# 1u_panel.net
KiCad netlist of a schematic drawn in EAGLE
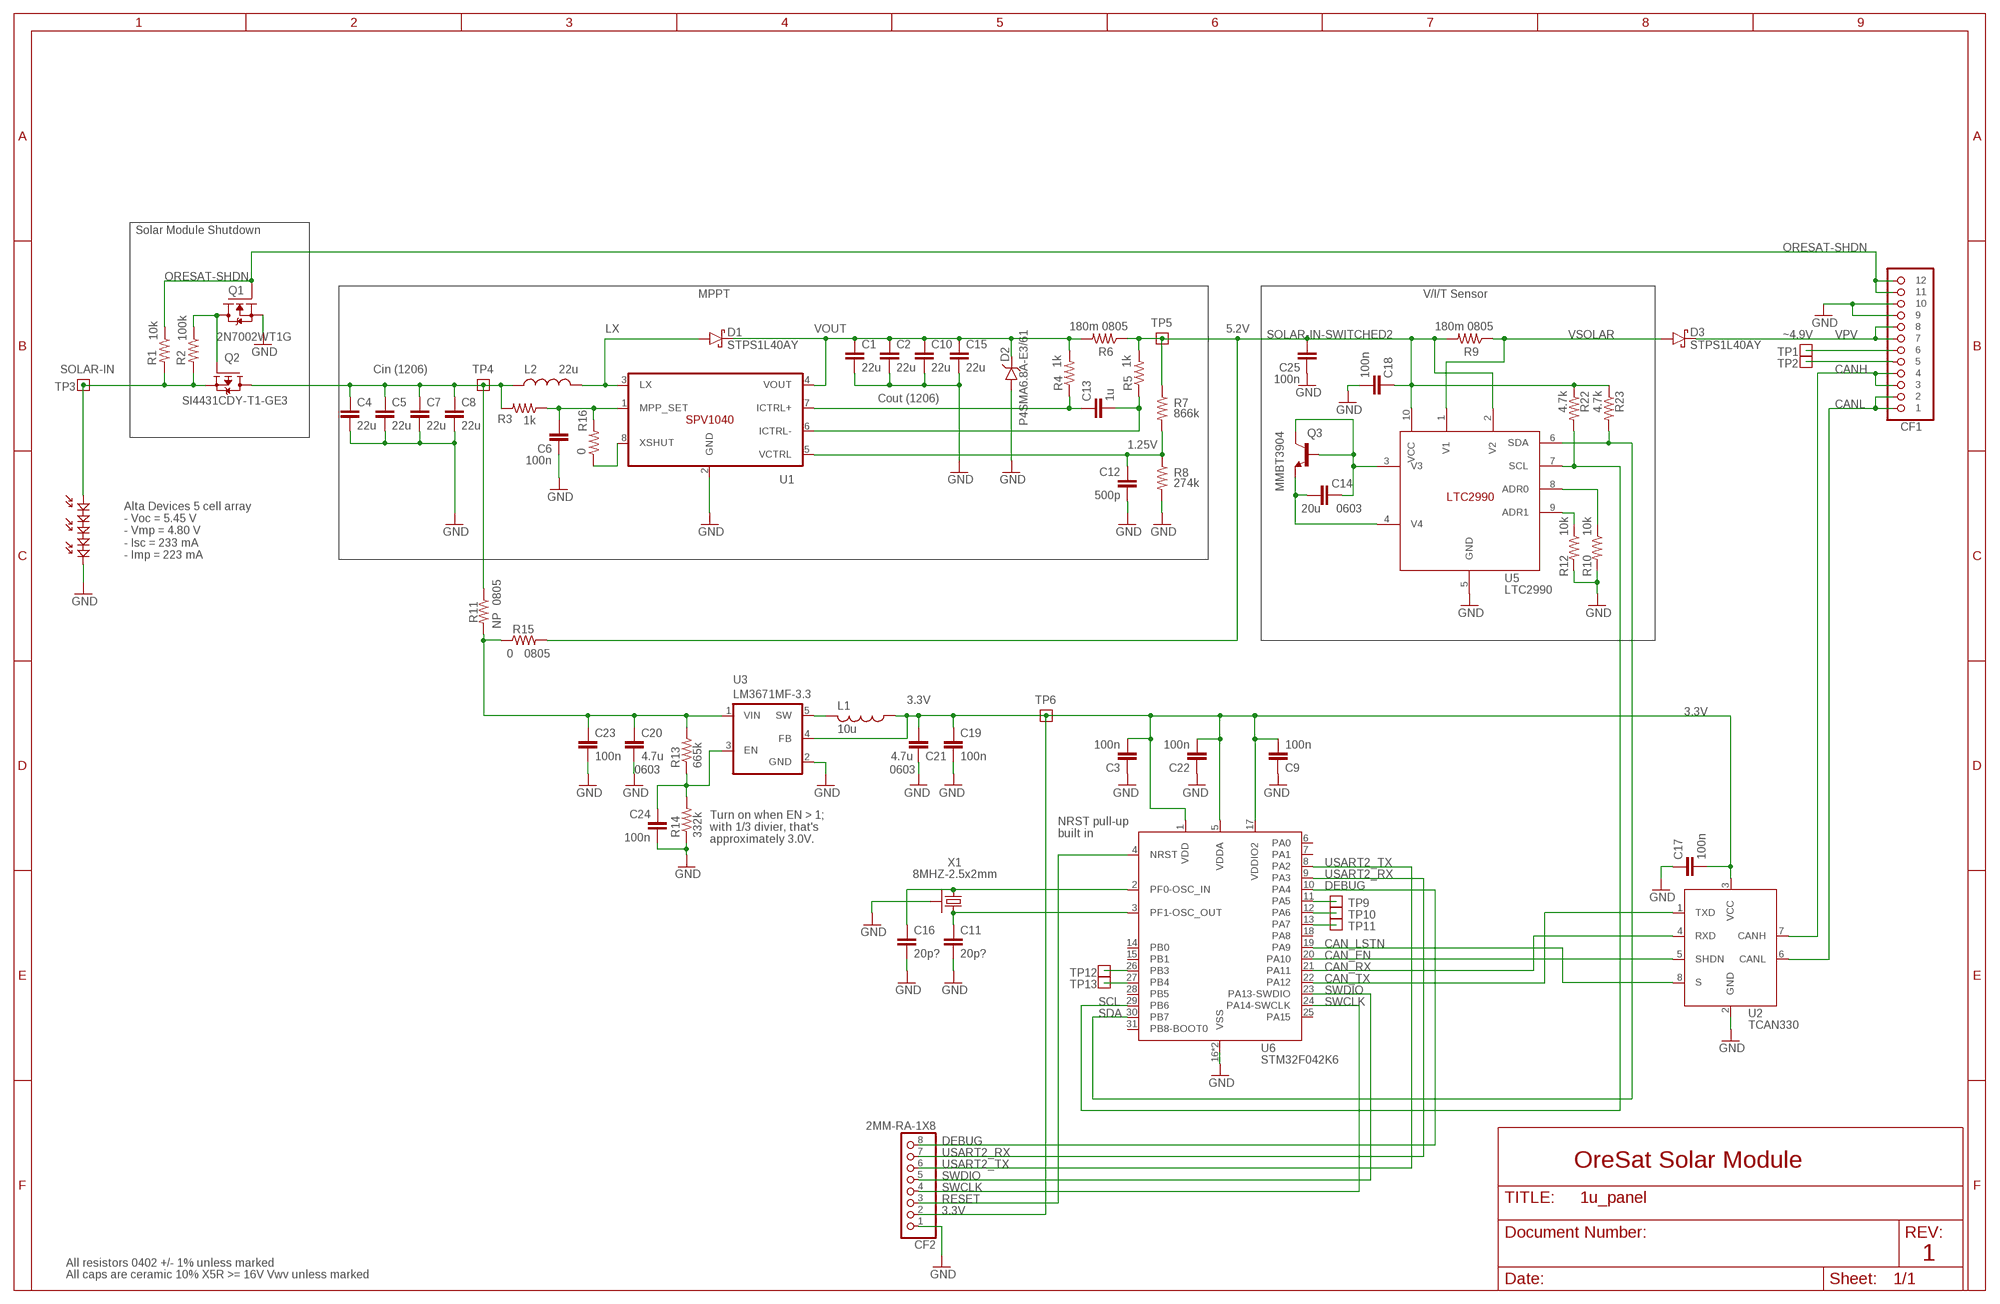
[diagram p0: schematic, sheet 1]

(export (version "E")
  (design (tool "Eeschema 10.0.6"))
  (components
    (comp (ref "C1")
      (value "22u")
      (footprint "eagle-import:1206-B")
      (fields (field (name "MFR") "Murata") (field (name "MPN") "GRM31CR71A226KE15L"))
      (libsource (lib "eagle-import") (part "C-EU1206-B"))
    )
    (comp (ref "C2")
      (value "22u")
      (footprint "eagle-import:1206-B")
      (fields (field (name "MFR") "Murata") (field (name "MPN") "GRM31CR71A226KE15L"))
      (libsource (lib "eagle-import") (part "C-EU1206-B"))
    )
    (comp (ref "C3")
      (value "100n")
      (footprint "eagle-import:.0402-B-NOSILK")
      (fields
        (field (name "MFR") "   Samsung Electro-Mechanics America, Inc.")
        (field (name "MPN") "CL05B104KO5NNNC")
      )
      (libsource (lib "eagle-import") (part "C-EU0402-B-NOSILK"))
    )
    (comp (ref "C4")
      (value "22u")
      (footprint "eagle-import:1206-B")
      (fields (field (name "MFR") "Murata") (field (name "MPN") "GRM31CR71A226KE15L"))
      (libsource (lib "eagle-import") (part "C-EU1206-B"))
    )
    (comp (ref "C5")
      (value "22u")
      (footprint "eagle-import:1206-B")
      (fields (field (name "MFR") "Murata") (field (name "MPN") "GRM31CR71A226KE15L"))
      (libsource (lib "eagle-import") (part "C-EU1206-B"))
    )
    (comp (ref "C6")
      (value "100n")
      (footprint "eagle-import:.0402-B-NOSILK")
      (fields
        (field (name "MFR") "   Samsung Electro-Mechanics America, Inc. ")
        (field (name "MPN") " CL05B104KO5NNNC")
      )
      (libsource (lib "eagle-import") (part "C-EU0402-B-NOSILK"))
    )
    (comp (ref "C7")
      (value "22u")
      (footprint "eagle-import:1206-B")
      (fields (field (name "MFR") "Murata") (field (name "MPN") "GRM31CR71A226KE15L"))
      (libsource (lib "eagle-import") (part "C-EU1206-B"))
    )
    (comp (ref "C8")
      (value "22u")
      (footprint "eagle-import:1206-B")
      (fields (field (name "MFR") "Murata") (field (name "MPN") "GRM31CR71A226KE15L"))
      (libsource (lib "eagle-import") (part "C-EU1206-B"))
    )
    (comp (ref "C9")
      (value "100n")
      (footprint "eagle-import:.0402-B-NOSILK")
      (fields
        (field (name "MFR") "Samsung Electro-Mechanics America, Inc.")
        (field (name "MPN") " CL05B104KO5NNNC")
      )
      (libsource (lib "eagle-import") (part "C-EU0402-B-NOSILK"))
    )
    (comp (ref "C10")
      (value "22u")
      (footprint "eagle-import:1206-B")
      (fields (field (name "MFR") "Murata") (field (name "MPN") "GRM31CR71A226KE15L"))
      (libsource (lib "eagle-import") (part "C-EU1206-B"))
    )
    (comp (ref "C11")
      (value "20p?")
      (footprint "eagle-import:.0402-B-NOSILK")
      (libsource (lib "eagle-import") (part "C-EU0402-B-NOSILK"))
    )
    (comp (ref "C12")
      (value "500p")
      (footprint "eagle-import:.0402-B-NOSILK")
      (fields
        (field (name "MFR") "Samsung Electro-Mechanics America, Inc.")
        (field (name "MPN") "CL05B561KB5NNNC")
      )
      (libsource (lib "eagle-import") (part "C-EU0402-B-NOSILK"))
    )
    (comp (ref "C13")
      (value "1u")
      (footprint "eagle-import:.0402-B-NOSILK")
      (fields
        (field (name "MFR") "Samsung Electro-Mechanics America, Inc.")
        (field (name "MPN") " CL05A105KA5NQNC")
      )
      (libsource (lib "eagle-import") (part "C-EU0402-B-NOSILK"))
    )
    (comp (ref "C14")
      (value "20u")
      (footprint "eagle-import:.0603-B-NOSILK")
      (fields
        (field (name "MFR") "Samsung Electro-Mechanics America, Inc.")
        (field (name "MPN") " CL10A226MP8NUNE")
      )
      (libsource (lib "eagle-import") (part "C-EU0603-B-NOSILK"))
    )
    (comp (ref "C15")
      (value "22u")
      (footprint "eagle-import:1206-B")
      (fields (field (name "MFR") "Murata") (field (name "MPN") "GRM31CR71A226KE15L"))
      (libsource (lib "eagle-import") (part "C-EU1206-B"))
    )
    (comp (ref "C16")
      (value "20p?")
      (footprint "eagle-import:.0402-B-NOSILK")
      (libsource (lib "eagle-import") (part "C-EU0402-B-NOSILK"))
    )
    (comp (ref "C17")
      (value "100n")
      (footprint "eagle-import:.0402-B-NOSILK")
      (fields
        (field (name "MFR") "Samsung Electro-Mechanics America, Inc.")
        (field (name "MPN") "CL05B104KO5NNNC")
      )
      (libsource (lib "eagle-import") (part "C-EU0402-B-NOSILK"))
    )
    (comp (ref "C18")
      (value "100n")
      (footprint "eagle-import:.0402-B-NOSILK")
      (fields
        (field (name "MFR") "Samsung Electro-Mechanics America, Inc.")
        (field (name "MPN") "CL05B104KO5NNNC")
      )
      (libsource (lib "eagle-import") (part "C-EU0402-B-NOSILK"))
    )
    (comp (ref "C19")
      (value "100n")
      (footprint "eagle-import:.0402-B-NOSILK")
      (fields
        (field (name "MFR") "   Samsung Electro-Mechanics America, Inc.")
        (field (name "MPN") "CL05B104KO5NNNC")
      )
      (libsource (lib "eagle-import") (part "C-EU0402-B-NOSILK"))
    )
    (comp (ref "C20")
      (value "4.7u")
      (footprint "eagle-import:C0603")
      (fields
        (field (name "MFR") "Samsung Electro-Mechanics America, Inc.")
        (field (name "MPN") "CL05B104KO5NNNC")
      )
      (libsource (lib "eagle-import") (part "C-EUC0603"))
    )
    (comp (ref "C21")
      (value "4.7u")
      (footprint "eagle-import:C0603")
      (fields
        (field (name "MFR") "   Samsung Electro-Mechanics America, Inc. ")
        (field (name "MPN") "CL05B104KO5NNNC")
      )
      (libsource (lib "eagle-import") (part "C-EUC0603"))
    )
    (comp (ref "C22")
      (value "100n")
      (footprint "eagle-import:.0402-B-NOSILK")
      (fields
        (field (name "MFR") "Samsung Electro-Mechanics America, Inc.")
        (field (name "MPN") "CL05B104KO5NNNC")
      )
      (libsource (lib "eagle-import") (part "C-EU0402-B-NOSILK"))
    )
    (comp (ref "C23")
      (value "100n")
      (footprint "eagle-import:.0402-B-NOSILK")
      (fields
        (field (name "MFR") "Samsung Electro-Mechanics America, Inc.")
        (field (name "MPN") "CL05B104KO5NNNC")
      )
      (libsource (lib "eagle-import") (part "C-EU0402-B-NOSILK"))
    )
    (comp (ref "C24")
      (value "100n")
      (footprint "eagle-import:.0402-B-NOSILK")
      (fields
        (field (name "MFR") "Samsung Electro-Mechanics America, Inc.")
        (field (name "MPN") "CL05B104KO5NNNC")
      )
      (libsource (lib "eagle-import") (part "C-EU0402-B-NOSILK"))
    )
    (comp (ref "C25")
      (value "100n")
      (footprint "eagle-import:.0402-B-NOSILK")
      (fields
        (field (name "MFR") "Samsung Electro-Mechanics America, Inc.")
        (field (name "MPN") " CL05B104KO5NNNC")
      )
      (libsource (lib "eagle-import") (part "C-EU0402-B-NOSILK"))
    )
    (comp (ref "CF1")
      (value "ORESAT-SOLARPANEL-12PIN")
      (footprint "eagle-import:CON-1.27-F-HARTING-1522012X601XXX")
      (libsource (lib "eagle-import") (part "ORESAT-SOLARPANEL-12PIN"))
    )
    (comp (ref "CF2")
      (value "2MM-RA-1X8")
      (footprint "eagle-import:CF-2MM-RA-1X8-PRECIDIP-831")
      (fields (field (name "MPN") "831-87-050-40-001101"))
      (libsource (lib "eagle-import") (part "2MM-RA-1X8"))
    )
    (comp (ref "D1")
      (value "STPS1L40AY")
      (footprint "eagle-import:DO214AC")
      (fields (field (name "MFR") "ST"))
      (libsource (lib "eagle-import") (part "DIODE-DO214AC"))
    )
    (comp (ref "D2")
      (value "P4SMA6.8A-E3/61")
      (footprint "eagle-import:DO214AC")
      (fields (field (name "MFR") "Vishay"))
      (libsource (lib "eagle-import") (part "diode-zener-tvs_DIODE-DO214AC"))
    )
    (comp (ref "D3")
      (value "STPS1L40AY")
      (footprint "eagle-import:DO214AC")
      (fields (field (name "MFR") "ST"))
      (libsource (lib "eagle-import") (part "DIODE-DO214AC"))
    )
    (comp (ref "L1")
      (value "10u")
      (footprint "eagle-import:L2012C")
      (fields (field (name "MFR") "Taiyo Yuden") (field (name "MPN") " CB2012T100KR"))
      (libsource (lib "eagle-import") (part "L-USL2012C"))
    )
    (comp (ref "L2")
      (value "22u")
      (footprint "eagle-import:VISHAY-DALE-IFSR-1515AHER")
      (fields (field (name "MFR") "Vishay Dale") (field (name "MPN") "IFSC1515AHER220M01"))
      (libsource (lib "eagle-import") (part "L-VISHAY-DALE-IFSC-1515AHER"))
    )
    (comp (ref "PV1")
      (value "ALTA-5-CELL-ARRAYALTA-FIVE-CELL-SLOT")
      (footprint "eagle-import:ALTA-FIVE-CELL-THROUGH-SLOT")
      (libsource (lib "eagle-import") (part "ALTA-5-CELL-ARRAYALTA-FIVE-CELL-SLOT"))
    )
    (comp (ref "Q1")
      (value "2N7002WT1G")
      (footprint "eagle-import:SOT23")
      (fields (field (name "MFR") "rer   ON Semiconductor"))
      (libsource (lib "eagle-import") (part "ON-N-CHANNEL-FET"))
    )
    (comp (ref "Q2")
      (value "SI4431CDY-T1-GE3")
      (footprint "eagle-import:SO8")
      (fields (field (name "MFR") "Vishay Siliconix") (field (name "MPN") "   SI4431CDY-T1-GE3"))
      (libsource (lib "eagle-import") (part "P-CHANNELFET"))
    )
    (comp (ref "Q3")
      (value "MMBT3904")
      (footprint "eagle-import:SOT23HOLE")
      (fields (field (name "MFR") "   Fairchild/ON Semiconductor"))
      (libsource (lib "eagle-import") (part "DIODE-INC-NPNSOT23HOLE"))
    )
    (comp (ref "R1")
      (value "10k")
      (footprint "eagle-import:.0402-B-NOSILK")
      (fields (field (name "MFR") "Rohm Semiconductor") (field (name "MPN") "MCR01MZPF1002"))
      (libsource (lib "eagle-import") (part "R-US_0402-B-NOSILK"))
    )
    (comp (ref "R2")
      (value "100k")
      (footprint "eagle-import:.0402-B-NOSILK")
      (fields (field (name "MFR") "Rohm Semiconductor") (field (name "MPN") "MCR01MRTF1003"))
      (libsource (lib "eagle-import") (part "R-US_0402-B-NOSILK"))
    )
    (comp (ref "R3")
      (value "1k")
      (footprint "eagle-import:.0402-B-NOSILK")
      (fields (field (name "MPN") " MCR01MZPF1001"))
      (libsource (lib "eagle-import") (part "R-US_0402-B-NOSILK"))
    )
    (comp (ref "R4")
      (value "1k")
      (footprint "eagle-import:.0402-B-NOSILK")
      (libsource (lib "eagle-import") (part "R-US_0402-B-NOSILK"))
    )
    (comp (ref "R5")
      (value "1k")
      (footprint "eagle-import:.0402-B-NOSILK")
      (libsource (lib "eagle-import") (part "R-US_0402-B-NOSILK"))
    )
    (comp (ref "R6")
      (value "180m 0805")
      (footprint "eagle-import:.0805-B-NOSILK")
      (fields (field (name "MFR") "Vishay Dale") (field (name "MPN") "RCWE0805R180FKEA"))
      (libsource (lib "eagle-import") (part "R-US_0805-B-NOSILK"))
    )
    (comp (ref "R7")
      (value "866k")
      (footprint "eagle-import:.0402-B-NOSILK")
      (fields (field (name "MPN") "RC1005F8663CS"))
      (libsource (lib "eagle-import") (part "R-US_0402-B-NOSILK"))
    )
    (comp (ref "R8")
      (value "274k")
      (footprint "eagle-import:.0402-B-NOSILK")
      (fields (field (name "MFR") "Vishay Dale") (field (name "MPN") "CRCW0402274KFKED"))
      (libsource (lib "eagle-import") (part "R-US_0402-B-NOSILK"))
    )
    (comp (ref "R9")
      (value "180m 0805")
      (footprint "eagle-import:.0805-B-NOSILK")
      (fields (field (name "MFR") "Vishay Dale") (field (name "MPN") "RCWE0805R180FKEA"))
      (libsource (lib "eagle-import") (part "R-US_0805-B-NOSILK"))
    )
    (comp (ref "R10")
      (value "10k")
      (footprint "eagle-import:.0402-B-NOSILK")
      (fields (field (name "MFR") "Rohm Semiconductor") (field (name "MPN") " MCR01MZPF1002"))
      (libsource (lib "eagle-import") (part "R-US_0402-B-NOSILK"))
    )
    (comp (ref "R11")
      (value "NP")
      (footprint "eagle-import:.0805-B-NOSILK")
      (libsource (lib "eagle-import") (part "R-US_0805-B-NOSILK"))
    )
    (comp (ref "R12")
      (value "10k")
      (footprint "eagle-import:.0402-B-NOSILK")
      (fields (field (name "MFR") "Rohm Semiconductor") (field (name "MPN") "MCR01MZPF1002"))
      (libsource (lib "eagle-import") (part "R-US_0402-B-NOSILK"))
    )
    (comp (ref "R13")
      (value "665k")
      (footprint "eagle-import:.0402-B-NOSILK")
      (fields
        (field (name "MFR") "Samsung Electro-Mechanics America, Inc.")
        (field (name "MPN") "RC1005F6653CS")
      )
      (libsource (lib "eagle-import") (part "R-US_0402-B-NOSILK"))
    )
    (comp (ref "R14")
      (value "332k")
      (footprint "eagle-import:.0402-B-NOSILK")
      (fields
        (field (name "MFR") "Samsung Electro-Mechanics America, Inc.")
        (field (name "MPN") " RC1005F3323CS")
      )
      (libsource (lib "eagle-import") (part "R-US_0402-B-NOSILK"))
    )
    (comp (ref "R15")
      (value "0")
      (footprint "eagle-import:.0805-B-NOSILK")
      (libsource (lib "eagle-import") (part "R-US_0805-B-NOSILK"))
    )
    (comp (ref "R16")
      (value "0")
      (footprint "eagle-import:.0402-B-NOSILK")
      (libsource (lib "eagle-import") (part "R-US_0402-B-NOSILK"))
    )
    (comp (ref "R22")
      (value "4.7k")
      (footprint "eagle-import:.0402-B-NOSILK")
      (fields (field (name "MFR") "Rohm Semiconductor") (field (name "MPN") "TRR01MZPF4701"))
      (libsource (lib "eagle-import") (part "R-US_0402-B-NOSILK"))
    )
    (comp (ref "R23")
      (value "4.7k")
      (footprint "eagle-import:.0402-B-NOSILK")
      (fields (field (name "MFR") "Rohm Semiconductor") (field (name "MPN") "TRR01MZPF4701"))
      (libsource (lib "eagle-import") (part "R-US_0402-B-NOSILK"))
    )
    (comp (ref "TP1")
      (value "TEST-POINT")
      (footprint "eagle-import:2MM-TEST-POINT")
      (libsource (lib "eagle-import") (part "TEST-POINT"))
    )
    (comp (ref "TP2")
      (value "TEST-POINT")
      (footprint "eagle-import:2MM-TEST-POINT")
      (libsource (lib "eagle-import") (part "TEST-POINT"))
    )
    (comp (ref "TP3")
      (value "TEST-POINT")
      (footprint "eagle-import:2MM-TEST-POINT")
      (libsource (lib "eagle-import") (part "TEST-POINT"))
    )
    (comp (ref "TP4")
      (value "TEST-POINT")
      (footprint "eagle-import:2MM-TEST-POINT")
      (libsource (lib "eagle-import") (part "TEST-POINT"))
    )
    (comp (ref "TP5")
      (value "TEST-POINT")
      (footprint "eagle-import:2MM-TEST-POINT")
      (libsource (lib "eagle-import") (part "TEST-POINT"))
    )
    (comp (ref "TP6")
      (value "TEST-POINT")
      (footprint "eagle-import:2MM-TEST-POINT")
      (libsource (lib "eagle-import") (part "TEST-POINT"))
    )
    (comp (ref "TP9")
      (value "TEST-POINT")
      (footprint "eagle-import:2MM-TEST-POINT")
      (libsource (lib "eagle-import") (part "TEST-POINT"))
    )
    (comp (ref "TP10")
      (value "TEST-POINT")
      (footprint "eagle-import:2MM-TEST-POINT")
      (libsource (lib "eagle-import") (part "TEST-POINT"))
    )
    (comp (ref "TP11")
      (value "TEST-POINT")
      (footprint "eagle-import:2MM-TEST-POINT")
      (libsource (lib "eagle-import") (part "TEST-POINT"))
    )
    (comp (ref "TP12")
      (value "TEST-POINT")
      (footprint "eagle-import:2MM-TEST-POINT")
      (libsource (lib "eagle-import") (part "TEST-POINT"))
    )
    (comp (ref "TP13")
      (value "TEST-POINT")
      (footprint "eagle-import:2MM-TEST-POINT")
      (libsource (lib "eagle-import") (part "TEST-POINT"))
    )
    (comp (ref "U1")
      (value "SPV1040")
      (footprint "eagle-import:TSSOP-8")
      (fields (field (name "MFR") "STMicroelectronics") (field (name "MPN") "SPV1040T"))
      (libsource (lib "eagle-import") (part "SPV1040"))
    )
    (comp (ref "U2")
      (value "TCAN330")
      (footprint "eagle-import:SOT23-8_TI-DCN")
      (fields (field (name "MFR") "Texas Instruments") (field (name "MPN") "TCAN330GDCNT"))
      (libsource (lib "eagle-import") (part "TCAN330"))
    )
    (comp (ref "U3")
      (value "LM3671MF-3.3")
      (footprint "eagle-import:SOT23-5")
      (libsource (lib "eagle-import") (part "LM3761"))
    )
    (comp (ref "U5")
      (value "LTC2990")
      (footprint "eagle-import:MSOP10")
      (fields (field (name "MFR") "Linear Technology") (field (name "MPN") " LTC2990CMS#PBF"))
      (libsource (lib "eagle-import") (part "LTC2990"))
    )
    (comp (ref "U6")
      (value "STM32F042K6")
      (footprint "eagle-import:QFP32-7X7")
      (fields (field (name "MFR") "STMicroelectronics") (field (name "MPN") "STM32F042K6T6"))
      (libsource (lib "eagle-import") (part "STM32F042K6"))
    )
    (comp (ref "X1")
      (value "8MHZ-2.5x2mm")
      (footprint "eagle-import:CRYSTAL_2.5X2")
      (fields (field (name "MFR") "ECS Inc.") (field (name "MPN") "ECS-80-18-20BQ-DS"))
      (libsource (lib "eagle-import") (part "CRYSTAL-WITH-GND"))
    )
  )
  (nets
    (net (code "1") (name "/3.3V") (class "Default")
      (node (ref "C17") (pin "2") (pinfunction "2_2") (pintype "passive"))
      (node (ref "C19") (pin "1") (pinfunction "1_1") (pintype "passive"))
      (node (ref "C21") (pin "1") (pinfunction "1_1") (pintype "passive"))
      (node (ref "C22") (pin "2") (pinfunction "2_2") (pintype "passive"))
      (node (ref "C3") (pin "2") (pinfunction "2_2") (pintype "passive"))
      (node (ref "C9") (pin "2") (pinfunction "2_2") (pintype "passive"))
      (node (ref "CF2") (pin "2") (pinfunction "2_2") (pintype "passive"))
      (node (ref "L1") (pin "1") (pinfunction "1_1") (pintype "passive"))
      (node (ref "TP6") (pin "1") (pinfunction "1_1") (pintype "passive"))
      (node (ref "U2") (pin "3") (pinfunction "VCC_3") (pintype "power_in"))
      (node (ref "U3") (pin "4") (pinfunction "FB_4") (pintype "input"))
      (node (ref "U6") (pin "1") (pinfunction "VDD_1") (pintype "power_in"))
      (node (ref "U6") (pin "17") (pinfunction "VDDIO2_17") (pintype "power_in"))
      (node (ref "U6") (pin "5") (pinfunction "VDDA_5") (pintype "power_in"))
    )
    (net (code "2") (name "/CANH") (class "Default")
      (node (ref "CF1") (pin "3") (pinfunction "3_3") (pintype "passive"))
      (node (ref "CF1") (pin "4") (pinfunction "4_4") (pintype "passive"))
      (node (ref "U2") (pin "7") (pinfunction "CANH_7") (pintype "bidirectional"))
    )
    (net (code "3") (name "/CANL") (class "Default")
      (node (ref "CF1") (pin "1") (pinfunction "1_1") (pintype "passive"))
      (node (ref "CF1") (pin "2") (pinfunction "2_2") (pintype "passive"))
      (node (ref "U2") (pin "6") (pinfunction "CANL_6") (pintype "bidirectional"))
    )
    (net (code "4") (name "/CAN_EN") (class "Default")
      (node (ref "U2") (pin "5") (pinfunction "SHDN_5") (pintype "input"))
      (node (ref "U6") (pin "20") (pinfunction "PA10_20") (pintype "bidirectional"))
    )
    (net (code "5") (name "/CAN_LSTN") (class "Default")
      (node (ref "U2") (pin "8") (pinfunction "S_8") (pintype "input"))
      (node (ref "U6") (pin "19") (pinfunction "PA9_19") (pintype "bidirectional"))
    )
    (net (code "6") (name "/CAN_RX") (class "Default")
      (node (ref "U2") (pin "4") (pinfunction "RXD_4") (pintype "output"))
      (node (ref "U6") (pin "21") (pinfunction "PA11_21") (pintype "bidirectional"))
    )
    (net (code "7") (name "/CAN_TX") (class "Default")
      (node (ref "U2") (pin "1") (pinfunction "TXD_1") (pintype "input"))
      (node (ref "U6") (pin "22") (pinfunction "PA12_22") (pintype "bidirectional"))
    )
    (net (code "8") (name "/DEBUG") (class "Default")
      (node (ref "CF2") (pin "8") (pinfunction "8_8") (pintype "passive"))
      (node (ref "U6") (pin "10") (pinfunction "PA4_10") (pintype "bidirectional"))
    )
    (net (code "9") (name "/LX") (class "Default")
      (node (ref "D1") (pin "A") (pinfunction "A_A") (pintype "passive"))
      (node (ref "L2") (pin "1") (pinfunction "1_1") (pintype "passive"))
      (node (ref "U1") (pin "3") (pinfunction "LX_3") (pintype "input"))
    )
    (net (code "10") (name "/ORESAT-SHDN") (class "Default")
      (node (ref "CF1") (pin "11") (pinfunction "11_11") (pintype "passive"))
      (node (ref "CF1") (pin "12") (pinfunction "12_12") (pintype "passive"))
      (node (ref "Q1") (pin "1") (pinfunction "G_1") (pintype "passive"))
      (node (ref "R1") (pin "1") (pinfunction "1_1") (pintype "passive"))
    )
    (net (code "11") (name "/RESET") (class "Default")
      (node (ref "CF2") (pin "3") (pinfunction "3_3") (pintype "passive"))
      (node (ref "U6") (pin "4") (pinfunction "NRST_4") (pintype "bidirectional"))
    )
    (net (code "12") (name "/SCL") (class "Default")
      (node (ref "R22") (pin "2") (pinfunction "2_2") (pintype "passive"))
      (node (ref "U5") (pin "7") (pinfunction "SCL_7") (pintype "bidirectional"))
      (node (ref "U6") (pin "29") (pinfunction "PB6_29") (pintype "bidirectional"))
    )
    (net (code "13") (name "/SDA") (class "Default")
      (node (ref "R23") (pin "2") (pinfunction "2_2") (pintype "passive"))
      (node (ref "U5") (pin "6") (pinfunction "SDA_6") (pintype "bidirectional"))
      (node (ref "U6") (pin "30") (pinfunction "PB7_30") (pintype "bidirectional"))
    )
    (net (code "14") (name "/SOLAR-IN") (class "Default")
      (node (ref "PV1") (pin "POS1") (pinfunction "POS_POS1") (pintype "power_in"))
      (node (ref "PV1") (pin "POS2") (pinfunction "POS_POS2") (pintype "power_in"))
      (node (ref "Q2") (pin "1") (pinfunction "S_1") (pintype "passive"))
      (node (ref "Q2") (pin "2") (pinfunction "S_2") (pintype "passive"))
      (node (ref "Q2") (pin "3") (pinfunction "S_3") (pintype "passive"))
      (node (ref "R1") (pin "2") (pinfunction "2_2") (pintype "passive"))
      (node (ref "R2") (pin "2") (pinfunction "2_2") (pintype "passive"))
      (node (ref "TP3") (pin "1") (pinfunction "1_1") (pintype "passive"))
    )
    (net (code "15") (name "/SOLAR-IN-SWITCHED2") (class "Default")
      (node (ref "C18") (pin "1") (pinfunction "1_1") (pintype "passive"))
      (node (ref "C25") (pin "2") (pinfunction "2_2") (pintype "passive"))
      (node (ref "R15") (pin "2") (pinfunction "2_2") (pintype "passive"))
      (node (ref "R22") (pin "1") (pinfunction "1_1") (pintype "passive"))
      (node (ref "R23") (pin "1") (pinfunction "1_1") (pintype "passive"))
      (node (ref "R5") (pin "2") (pinfunction "2_2") (pintype "passive"))
      (node (ref "R6") (pin "1") (pinfunction "1_1") (pintype "passive"))
      (node (ref "R7") (pin "1") (pinfunction "1_1") (pintype "passive"))
      (node (ref "R9") (pin "2") (pinfunction "2_2") (pintype "passive"))
      (node (ref "TP5") (pin "1") (pinfunction "1_1") (pintype "passive"))
      (node (ref "U5") (pin "10") (pinfunction "VCC_10") (pintype "bidirectional"))
      (node (ref "U5") (pin "2") (pinfunction "V2_2") (pintype "bidirectional"))
    )
    (net (code "16") (name "/SWCLK") (class "Default")
      (node (ref "CF2") (pin "4") (pinfunction "4_4") (pintype "passive"))
      (node (ref "U6") (pin "24") (pinfunction "PA14-SWCLK_24") (pintype "bidirectional"))
    )
    (net (code "17") (name "/SWDIO") (class "Default")
      (node (ref "CF2") (pin "5") (pinfunction "5_5") (pintype "passive"))
      (node (ref "U6") (pin "23") (pinfunction "PA13-SWDIO_23") (pintype "bidirectional"))
    )
    (net (code "18") (name "/USART2_RX") (class "Default")
      (node (ref "CF2") (pin "7") (pinfunction "7_7") (pintype "passive"))
      (node (ref "U6") (pin "9") (pinfunction "PA3_9") (pintype "bidirectional"))
    )
    (net (code "19") (name "/USART2_TX") (class "Default")
      (node (ref "CF2") (pin "6") (pinfunction "6_6") (pintype "passive"))
      (node (ref "U6") (pin "8") (pinfunction "PA2_8") (pintype "bidirectional"))
    )
    (net (code "20") (name "/VOUT") (class "Default")
      (node (ref "C1") (pin "1") (pinfunction "1_1") (pintype "passive"))
      (node (ref "C10") (pin "1") (pinfunction "1_1") (pintype "passive"))
      (node (ref "C15") (pin "1") (pinfunction "1_1") (pintype "passive"))
      (node (ref "C2") (pin "1") (pinfunction "1_1") (pintype "passive"))
      (node (ref "D1") (pin "C") (pinfunction "C_C") (pintype "passive"))
      (node (ref "D2") (pin "C") (pinfunction "C_C") (pintype "passive"))
      (node (ref "R4") (pin "2") (pinfunction "2_2") (pintype "passive"))
      (node (ref "R6") (pin "2") (pinfunction "2_2") (pintype "passive"))
      (node (ref "U1") (pin "4") (pinfunction "VOUT_4") (pintype "power_in"))
    )
    (net (code "21") (name "/VPV") (class "Default")
      (node (ref "CF1") (pin "7") (pinfunction "7_7") (pintype "passive"))
      (node (ref "CF1") (pin "8") (pinfunction "8_8") (pintype "passive"))
      (node (ref "D3") (pin "C") (pinfunction "C_C") (pintype "passive"))
    )
    (net (code "22") (name "/VSOLAR") (class "Default")
      (node (ref "D3") (pin "A") (pinfunction "A_A") (pintype "passive"))
      (node (ref "R9") (pin "1") (pinfunction "1_1") (pintype "passive"))
      (node (ref "U5") (pin "1") (pinfunction "V1_1") (pintype "bidirectional"))
    )
    (net (code "23") (name "GND") (class "Default")
      (node (ref "C1") (pin "2") (pinfunction "2_2") (pintype "passive"))
      (node (ref "C10") (pin "2") (pinfunction "2_2") (pintype "passive"))
      (node (ref "C11") (pin "2") (pinfunction "2_2") (pintype "passive"))
      (node (ref "C12") (pin "2") (pinfunction "2_2") (pintype "passive"))
      (node (ref "C15") (pin "2") (pinfunction "2_2") (pintype "passive"))
      (node (ref "C16") (pin "2") (pinfunction "2_2") (pintype "passive"))
      (node (ref "C17") (pin "1") (pinfunction "1_1") (pintype "passive"))
      (node (ref "C18") (pin "2") (pinfunction "2_2") (pintype "passive"))
      (node (ref "C19") (pin "2") (pinfunction "2_2") (pintype "passive"))
      (node (ref "C2") (pin "2") (pinfunction "2_2") (pintype "passive"))
      (node (ref "C20") (pin "2") (pinfunction "2_2") (pintype "passive"))
      (node (ref "C21") (pin "2") (pinfunction "2_2") (pintype "passive"))
      (node (ref "C22") (pin "1") (pinfunction "1_1") (pintype "passive"))
      (node (ref "C23") (pin "2") (pinfunction "2_2") (pintype "passive"))
      (node (ref "C24") (pin "2") (pinfunction "2_2") (pintype "passive"))
      (node (ref "C25") (pin "1") (pinfunction "1_1") (pintype "passive"))
      (node (ref "C3") (pin "1") (pinfunction "1_1") (pintype "passive"))
      (node (ref "C4") (pin "2") (pinfunction "2_2") (pintype "passive"))
      (node (ref "C5") (pin "2") (pinfunction "2_2") (pintype "passive"))
      (node (ref "C6") (pin "1") (pinfunction "1_1") (pintype "passive"))
      (node (ref "C7") (pin "2") (pinfunction "2_2") (pintype "passive"))
      (node (ref "C8") (pin "2") (pinfunction "2_2") (pintype "passive"))
      (node (ref "C9") (pin "1") (pinfunction "1_1") (pintype "passive"))
      (node (ref "CF1") (pin "10") (pinfunction "10_10") (pintype "passive"))
      (node (ref "CF1") (pin "9") (pinfunction "9_9") (pintype "passive"))
      (node (ref "CF2") (pin "1") (pinfunction "1_1") (pintype "passive"))
      (node (ref "D2") (pin "A") (pinfunction "A_A") (pintype "passive"))
      (node (ref "PV1") (pin "NEG1") (pinfunction "NEG_NEG1") (pintype "power_in"))
      (node (ref "PV1") (pin "NEG2") (pinfunction "NEG_NEG2") (pintype "power_in"))
      (node (ref "Q1") (pin "2") (pinfunction "S_2") (pintype "passive"))
      (node (ref "R10") (pin "2") (pinfunction "2_2") (pintype "passive"))
      (node (ref "R12") (pin "2") (pinfunction "2_2") (pintype "passive"))
      (node (ref "R14") (pin "1") (pinfunction "1_1") (pintype "passive"))
      (node (ref "R8") (pin "2") (pinfunction "2_2") (pintype "passive"))
      (node (ref "U1") (pin "2") (pinfunction "GND_2") (pintype "power_in"))
      (node (ref "U2") (pin "2") (pinfunction "GND_2") (pintype "power_in"))
      (node (ref "U3") (pin "2") (pinfunction "GND_2") (pintype "bidirectional"))
      (node (ref "U5") (pin "5") (pinfunction "GND_5") (pintype "bidirectional"))
      (node (ref "U6") (pin "16") (pinfunction "VSS_16") (pintype "power_in"))
      (node (ref "U6") (pin "32") (pinfunction "VSS_32") (pintype "power_in"))
      (node (ref "X1") (pin "2") (pinfunction "SHIELD_2") (pintype "power_in"))
      (node (ref "X1") (pin "4") (pinfunction "SHIELD_4") (pintype "power_in"))
    )
    (net (code "24") (name "Net-(C4-Pad1)") (class "Default")
      (node (ref "C4") (pin "1") (pinfunction "1_1") (pintype "passive"))
      (node (ref "C5") (pin "1") (pinfunction "1_1") (pintype "passive"))
      (node (ref "C7") (pin "1") (pinfunction "1_1") (pintype "passive"))
      (node (ref "C8") (pin "1") (pinfunction "1_1") (pintype "passive"))
      (node (ref "L2") (pin "2") (pinfunction "2_2") (pintype "passive"))
      (node (ref "Q2") (pin "5") (pinfunction "D_5") (pintype "passive"))
      (node (ref "Q2") (pin "6") (pinfunction "D_6") (pintype "passive"))
      (node (ref "Q2") (pin "7") (pinfunction "D_7") (pintype "passive"))
      (node (ref "Q2") (pin "8") (pinfunction "D_8") (pintype "passive"))
      (node (ref "R11") (pin "1") (pinfunction "1_1") (pintype "passive"))
      (node (ref "R3") (pin "2") (pinfunction "2_2") (pintype "passive"))
      (node (ref "TP4") (pin "1") (pinfunction "1_1") (pintype "passive"))
    )
    (net (code "25") (name "Net-(CF1-Pad5)") (class "Default")
      (node (ref "CF1") (pin "5") (pinfunction "5_5") (pintype "passive"))
      (node (ref "TP2") (pin "1") (pinfunction "1_1") (pintype "passive"))
    )
    (net (code "26") (name "Net-(CF1-Pad6)") (class "Default")
      (node (ref "CF1") (pin "6") (pinfunction "6_6") (pintype "passive"))
      (node (ref "TP1") (pin "1") (pinfunction "1_1") (pintype "passive"))
    )
    (net (code "27") (name "Net-(Q1-D)") (class "Default")
      (node (ref "Q1") (pin "3") (pinfunction "D_3") (pintype "passive"))
      (node (ref "Q2") (pin "4") (pinfunction "G_4") (pintype "passive"))
      (node (ref "R2") (pin "1") (pinfunction "1_1") (pintype "passive"))
    )
    (net (code "28") (name "Net-(Q3-B)") (class "Default")
      (node (ref "C14") (pin "2") (pinfunction "2_2") (pintype "passive"))
      (node (ref "Q3") (pin "1") (pinfunction "B_1") (pintype "passive"))
      (node (ref "Q3") (pin "3") (pinfunction "C_3") (pintype "passive"))
      (node (ref "U5") (pin "3") (pinfunction "V3_3") (pintype "bidirectional"))
    )
    (net (code "29") (name "Net-(Q3-E)") (class "Default")
      (node (ref "C14") (pin "1") (pinfunction "1_1") (pintype "passive"))
      (node (ref "Q3") (pin "2") (pinfunction "E_2") (pintype "passive"))
      (node (ref "U5") (pin "4") (pinfunction "V4_4") (pintype "bidirectional"))
    )
    (net (code "30") (name "Net-(U1-ICTRL+)") (class "Default")
      (node (ref "C13") (pin "2") (pinfunction "2_2") (pintype "passive"))
      (node (ref "R4") (pin "1") (pinfunction "1_1") (pintype "passive"))
      (node (ref "U1") (pin "7") (pinfunction "ICTRL+_7") (pintype "input"))
    )
    (net (code "31") (name "Net-(U1-ICTRL-)") (class "Default")
      (node (ref "C13") (pin "1") (pinfunction "1_1") (pintype "passive"))
      (node (ref "R5") (pin "1") (pinfunction "1_1") (pintype "passive"))
      (node (ref "U1") (pin "6") (pinfunction "ICTRL-_6") (pintype "input"))
    )
    (net (code "32") (name "Net-(U1-MPP_SET)") (class "Default")
      (node (ref "C6") (pin "2") (pinfunction "2_2") (pintype "passive"))
      (node (ref "R16") (pin "2") (pinfunction "2_2") (pintype "passive"))
      (node (ref "R3") (pin "1") (pinfunction "1_1") (pintype "passive"))
      (node (ref "U1") (pin "1") (pinfunction "MPP_SET_1") (pintype "input"))
    )
    (net (code "33") (name "Net-(U1-VCTRL)") (class "Default")
      (node (ref "C12") (pin "1") (pinfunction "1_1") (pintype "passive"))
      (node (ref "R7") (pin "2") (pinfunction "2_2") (pintype "passive"))
      (node (ref "R8") (pin "1") (pinfunction "1_1") (pintype "passive"))
      (node (ref "U1") (pin "5") (pinfunction "VCTRL_5") (pintype "input"))
    )
    (net (code "34") (name "Net-(U1-XSHUT)") (class "Default")
      (node (ref "R16") (pin "1") (pinfunction "1_1") (pintype "passive"))
      (node (ref "U1") (pin "8") (pinfunction "XSHUT_8") (pintype "input"))
    )
    (net (code "35") (name "Net-(U3-EN)") (class "Default")
      (node (ref "C24") (pin "1") (pinfunction "1_1") (pintype "passive"))
      (node (ref "R13") (pin "1") (pinfunction "1_1") (pintype "passive"))
      (node (ref "R14") (pin "2") (pinfunction "2_2") (pintype "passive"))
      (node (ref "U3") (pin "3") (pinfunction "EN_3") (pintype "input"))
    )
    (net (code "36") (name "Net-(U3-SW)") (class "Default")
      (node (ref "L1") (pin "2") (pinfunction "2_2") (pintype "passive"))
      (node (ref "U3") (pin "5") (pinfunction "SW_5") (pintype "bidirectional"))
    )
    (net (code "37") (name "Net-(U3-VIN)") (class "Default")
      (node (ref "C20") (pin "1") (pinfunction "1_1") (pintype "passive"))
      (node (ref "C23") (pin "1") (pinfunction "1_1") (pintype "passive"))
      (node (ref "R11") (pin "2") (pinfunction "2_2") (pintype "passive"))
      (node (ref "R13") (pin "2") (pinfunction "2_2") (pintype "passive"))
      (node (ref "R15") (pin "1") (pinfunction "1_1") (pintype "passive"))
      (node (ref "U3") (pin "1") (pinfunction "VIN_1") (pintype "bidirectional"))
    )
    (net (code "38") (name "Net-(U5-ADR0)") (class "Default")
      (node (ref "R10") (pin "1") (pinfunction "1_1") (pintype "passive"))
      (node (ref "U5") (pin "8") (pinfunction "ADR0_8") (pintype "bidirectional"))
    )
    (net (code "39") (name "Net-(U5-ADR1)") (class "Default")
      (node (ref "R12") (pin "1") (pinfunction "1_1") (pintype "passive"))
      (node (ref "U5") (pin "9") (pinfunction "ADR1_9") (pintype "bidirectional"))
    )
    (net (code "40") (name "Net-(U6-PA5)") (class "Default")
      (node (ref "TP9") (pin "1") (pinfunction "1_1") (pintype "passive"))
      (node (ref "U6") (pin "11") (pinfunction "PA5_11") (pintype "bidirectional"))
    )
    (net (code "41") (name "Net-(U6-PA6)") (class "Default")
      (node (ref "TP10") (pin "1") (pinfunction "1_1") (pintype "passive"))
      (node (ref "U6") (pin "12") (pinfunction "PA6_12") (pintype "bidirectional"))
    )
    (net (code "42") (name "Net-(U6-PA7)") (class "Default")
      (node (ref "TP11") (pin "1") (pinfunction "1_1") (pintype "passive"))
      (node (ref "U6") (pin "13") (pinfunction "PA7_13") (pintype "bidirectional"))
    )
    (net (code "43") (name "Net-(U6-PB3)") (class "Default")
      (node (ref "TP12") (pin "1") (pinfunction "1_1") (pintype "passive"))
      (node (ref "U6") (pin "26") (pinfunction "PB3_26") (pintype "bidirectional"))
    )
    (net (code "44") (name "Net-(U6-PB4)") (class "Default")
      (node (ref "TP13") (pin "1") (pinfunction "1_1") (pintype "passive"))
      (node (ref "U6") (pin "27") (pinfunction "PB4_27") (pintype "bidirectional"))
    )
    (net (code "45") (name "Net-(U6-PF0-OSC_IN)") (class "Default")
      (node (ref "C16") (pin "1") (pinfunction "1_1") (pintype "passive"))
      (node (ref "U6") (pin "2") (pinfunction "PF0-OSC_IN_2") (pintype "bidirectional"))
      (node (ref "X1") (pin "1") (pinfunction "1_1") (pintype "passive"))
    )
    (net (code "46") (name "Net-(U6-PF1-OSC_OUT)") (class "Default")
      (node (ref "C11") (pin "1") (pinfunction "1_1") (pintype "passive"))
      (node (ref "U6") (pin "3") (pinfunction "PF1-OSC_OUT_3") (pintype "bidirectional"))
      (node (ref "X1") (pin "3") (pinfunction "2_3") (pintype "passive"))
    )
    (net (code "47") (name "unconnected-(U6-PA0-Pad6)") (class "Default")
      (node (ref "U6") (pin "6") (pinfunction "PA0_6") (pintype "bidirectional"))
    )
    (net (code "48") (name "unconnected-(U6-PA1-Pad7)") (class "Default")
      (node (ref "U6") (pin "7") (pinfunction "PA1_7") (pintype "bidirectional"))
    )
    (net (code "49") (name "unconnected-(U6-PA8-Pad18)") (class "Default")
      (node (ref "U6") (pin "18") (pinfunction "PA8_18") (pintype "bidirectional"))
    )
    (net (code "50") (name "unconnected-(U6-PA15-Pad25)") (class "Default")
      (node (ref "U6") (pin "25") (pinfunction "PA15_25") (pintype "bidirectional"))
    )
    (net (code "51") (name "unconnected-(U6-PB0-Pad14)") (class "Default")
      (node (ref "U6") (pin "14") (pinfunction "PB0_14") (pintype "bidirectional"))
    )
    (net (code "52") (name "unconnected-(U6-PB1-Pad15)") (class "Default")
      (node (ref "U6") (pin "15") (pinfunction "PB1_15") (pintype "bidirectional"))
    )
    (net (code "53") (name "unconnected-(U6-PB5-Pad28)") (class "Default")
      (node (ref "U6") (pin "28") (pinfunction "PB5_28") (pintype "bidirectional"))
    )
    (net (code "54") (name "unconnected-(U6-PB8-BOOT0-Pad31)") (class "Default")
      (node (ref "U6") (pin "31") (pinfunction "PB8-BOOT0_31") (pintype "bidirectional"))
    )
  )
)
